# USB.net
KiCad netlist of a schematic drawn in Altium Designer
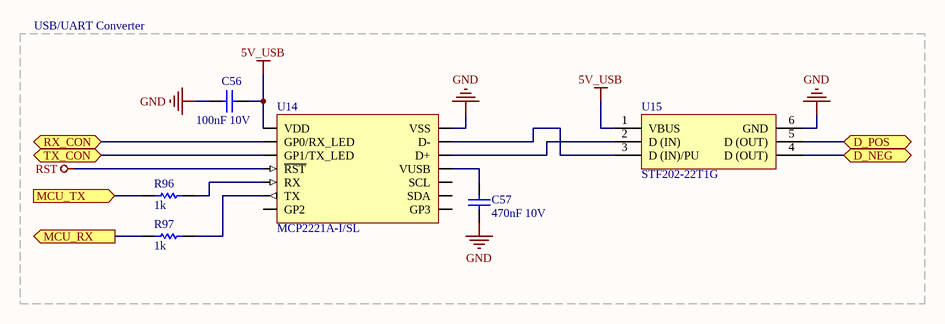
[diagram p0: USB.SchDoc]

(export (version "E")
  (design (tool "Eeschema 10.0.6"))
  (components
    (comp (ref "C56")
      (value "100nF 10V")
      (footprint "0402")
      (description "Capacitor")
      (fields (field (name "PARTNUMBER") "CAP.100n.10V.20%.SMD.0402") (field (name "MANUFACTURER") "Wurth"))
      (libsource (lib "IntLib") (part "Cap"))
    )
    (comp (ref "C57")
      (value "470nF 10V")
      (footprint "1608[0603]")
      (description "Capacitor")
      (fields (field (name "PARTNUMBER") "CAP.470n.10V.20%.SMD.0603") (field (name "MANUFACTURER") "Vishay"))
      (libsource (lib "IntLib") (part "Cap"))
    )
    (comp (ref "R96")
      (value "1k")
      (footprint "6-0805_M")
      (description "Resistor")
      (fields (field (name "PARTNUMBER") "RES.1K.1/8W.5%.SMD.0805") (field (name "MANUFACTURER") "Yageo"))
      (libsource (lib "IntLib") (part "Res"))
    )
    (comp (ref "R97")
      (value "1k")
      (footprint "6-0805_M")
      (description "Resistor")
      (fields (field (name "PARTNUMBER") "RES.1K.1/8W.5%.SMD.0805") (field (name "MANUFACTURER") "Yageo"))
      (libsource (lib "IntLib") (part "Res"))
    )
    (comp (ref "U14")
      (value "MCP2221A-I/SL")
      (footprint "SOIC14_N")
      (description "USB Interface IC USB 2.0 to I2C Converter with GPIO")
      (fields (field (name "MANUFACTURER") "Microchip"))
      (libsource (lib "IntLib") (part "MCP2221A-I/SL"))
    )
    (comp (ref "U15")
      (value "STF202-22T1G")
      (footprint "SOP6")
      (fields (field (name "MANUFACTURER") "ON Semiconductor"))
      (libsource (lib "IntLib") (part "STF202-22T1G"))
    )
  )
  (nets
    (net (code "1") (name "/D_NEG") (class "Default")
      (node (ref "U15") (pin "4") (pinfunction "D_(OUT)_4") (pintype "passive"))
    )
    (net (code "2") (name "/D_POS") (class "Default")
      (node (ref "U15") (pin "5") (pinfunction "D_(OUT)_5") (pintype "passive"))
    )
    (net (code "3") (name "/MCU_RX") (class "Default")
      (node (ref "R97") (pin "2") (pinfunction "2_2") (pintype "passive"))
    )
    (net (code "4") (name "/MCU_TX") (class "Default")
      (node (ref "R96") (pin "2") (pinfunction "2_2") (pintype "passive"))
    )
    (net (code "5") (name "/RX_CON") (class "Default")
      (node (ref "U14") (pin "2") (pinfunction "GP0/RX_LED_2") (pintype "bidirectional"))
    )
    (net (code "6") (name "/TX_CON") (class "Default")
      (node (ref "U14") (pin "3") (pinfunction "GP1/TX_LED_3") (pintype "bidirectional"))
    )
    (net (code "7") (name "5V_USB") (class "Default")
      (node (ref "C56") (pin "2") (pinfunction "2_2") (pintype "passive"))
      (node (ref "U14") (pin "1") (pinfunction "VDD_1") (pintype "power_in"))
      (node (ref "U15") (pin "1") (pinfunction "VBUS_1") (pintype "passive"))
    )
    (net (code "8") (name "GND") (class "Default")
      (node (ref "C56") (pin "1") (pinfunction "1_1") (pintype "passive"))
      (node (ref "C57") (pin "1") (pinfunction "1_1") (pintype "passive"))
      (node (ref "U14") (pin "14") (pinfunction "VSS_14") (pintype "power_in"))
      (node (ref "U15") (pin "6") (pinfunction "GND_6") (pintype "passive"))
    )
    (net (code "9") (name "Net-(U14-D+)") (class "Default")
      (node (ref "U14") (pin "13") (pinfunction "D+_13") (pintype "bidirectional"))
      (node (ref "U15") (pin "2") (pinfunction "D_(IN)_2") (pintype "passive"))
    )
    (net (code "10") (name "Net-(U14-D-)") (class "Default")
      (node (ref "U14") (pin "12") (pinfunction "D-_12") (pintype "bidirectional"))
      (node (ref "U15") (pin "3") (pinfunction "D_(IN)/PU_3") (pintype "passive"))
    )
    (net (code "11") (name "Net-(U14-RX)") (class "Default")
      (node (ref "R96") (pin "1") (pinfunction "1_1") (pintype "passive"))
      (node (ref "U14") (pin "5") (pinfunction "RX_5") (pintype "input"))
    )
    (net (code "12") (name "Net-(U14-TX)") (class "Default")
      (node (ref "R97") (pin "1") (pinfunction "1_1") (pintype "passive"))
      (node (ref "U14") (pin "6") (pinfunction "TX_6") (pintype "output"))
    )
    (net (code "13") (name "Net-(U14-VUSB)") (class "Default")
      (node (ref "C57") (pin "2") (pinfunction "2_2") (pintype "passive"))
      (node (ref "U14") (pin "11") (pinfunction "VUSB_11") (pintype "power_in"))
    )
    (net (code "14") (name "RST") (class "Default")
      (node (ref "U14") (pin "4") (pinfunction "~{RST}_4") (pintype "input"))
    )
    (net (code "15") (name "unconnected-(U14-GP2-Pad7)") (class "Default")
      (node (ref "U14") (pin "7") (pinfunction "GP2_7") (pintype "bidirectional"))
    )
    (net (code "16") (name "unconnected-(U14-GP3-Pad8)") (class "Default")
      (node (ref "U14") (pin "8") (pinfunction "GP3_8") (pintype "bidirectional"))
    )
    (net (code "17") (name "unconnected-(U14-SCL-Pad10)") (class "Default")
      (node (ref "U14") (pin "10") (pinfunction "SCL_10") (pintype "bidirectional"))
    )
    (net (code "18") (name "unconnected-(U14-SDA-Pad9)") (class "Default")
      (node (ref "U14") (pin "9") (pinfunction "SDA_9") (pintype "bidirectional"))
    )
  )
)
